# devkit.net
KiCad netlist of a schematic drawn in EAGLE
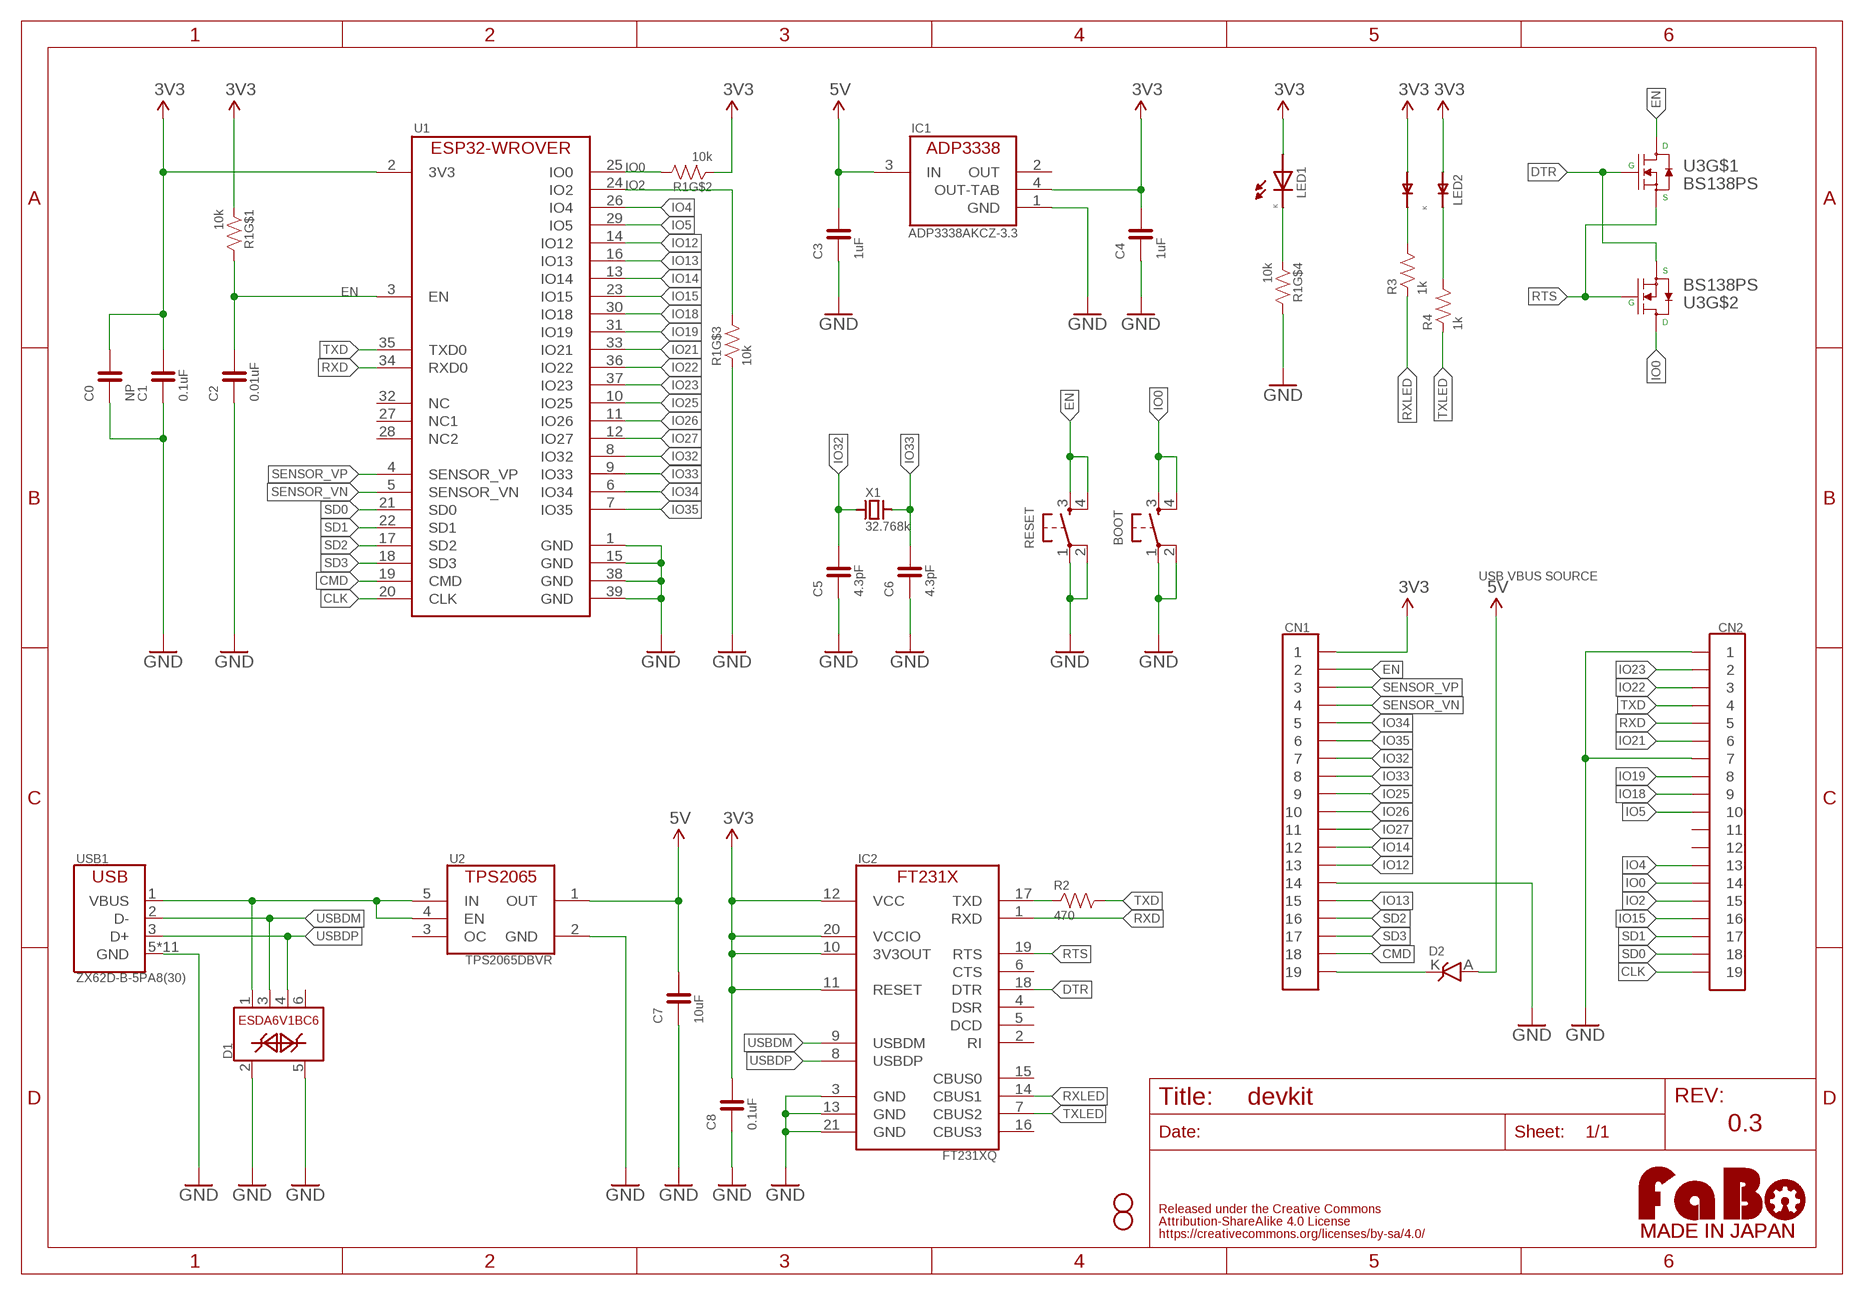
[diagram p0: schematic, sheet 1]

(export (version "E")
  (design (tool "Eeschema 10.0.6"))
  (components
    (comp (ref "BOOT")
      (value "TACTILE-KMR2")
      (footprint "eagle-import:KMR2-TACT")
      (libsource (lib "eagle-import") (part "TACTILE-KMR2"))
    )
    (comp (ref "C0")
      (value "NP")
      (footprint "eagle-import:MULTIPAD0603")
      (libsource (lib "eagle-import") (part "CAPACITOR-M"))
    )
    (comp (ref "C1")
      (value "0.1uF")
      (footprint "eagle-import:EIA0603")
      (libsource (lib "eagle-import") (part "CAPACITOR-0603"))
    )
    (comp (ref "C2")
      (value "0.01uF")
      (footprint "eagle-import:EIA0603")
      (libsource (lib "eagle-import") (part "CAPACITOR-0603"))
    )
    (comp (ref "C3")
      (value "1uF")
      (footprint "eagle-import:EIA0603")
      (libsource (lib "eagle-import") (part "CAPACITOR-0603"))
    )
    (comp (ref "C4")
      (value "1uF")
      (footprint "eagle-import:EIA0603")
      (libsource (lib "eagle-import") (part "CAPACITOR-0603"))
    )
    (comp (ref "C5")
      (value "4.3pF")
      (footprint "eagle-import:EIA0603")
      (libsource (lib "eagle-import") (part "CAPACITOR-0603"))
    )
    (comp (ref "C6")
      (value "4.3pF")
      (footprint "eagle-import:EIA0603")
      (libsource (lib "eagle-import") (part "CAPACITOR-0603"))
    )
    (comp (ref "C7")
      (value "10uF")
      (footprint "eagle-import:EIA0603")
      (libsource (lib "eagle-import") (part "CAPACITOR-0603"))
    )
    (comp (ref "C8")
      (value "0.1uF")
      (footprint "eagle-import:EIA0603")
      (libsource (lib "eagle-import") (part "CAPACITOR-0603"))
    )
    (comp (ref "CN1")
      (value "PIN_1X19")
      (footprint "eagle-import:PIN_1X19")
      (libsource (lib "eagle-import") (part "PIN_1X19"))
    )
    (comp (ref "CN2")
      (value "PIN_1X19")
      (footprint "eagle-import:PIN_1X19")
      (libsource (lib "eagle-import") (part "PIN_1X19"))
    )
    (comp (ref "D1")
      (value "ESDA6V1BC6")
      (footprint "eagle-import:SOT-23-6L")
      (libsource (lib "eagle-import") (part "ESDA6V1BC6"))
    )
    (comp (ref "D2")
      (value "DIODE_SCHOTTKY-RB161MM-20")
      (footprint "eagle-import:SOD-123FL_RB161MM-20")
      (libsource (lib "eagle-import") (part "DIODE_SCHOTTKY-RB161MM-20"))
    )
    (comp (ref "FID1")
      (value "FIDUCIAL-TOP")
      (footprint "eagle-import:FIDUCIAL_15_TOP")
      (libsource (lib "eagle-import") (part "FIDUCIAL-TOP"))
    )
    (comp (ref "FID2")
      (value "FIDUCIAL-TOP")
      (footprint "eagle-import:FIDUCIAL_15_TOP")
      (libsource (lib "eagle-import") (part "FIDUCIAL-TOP"))
    )
    (comp (ref "IC1")
      (value "ADP3338AKCZ-3.3")
      (footprint "eagle-import:SOT-223-KC3")
      (libsource (lib "eagle-import") (part "ADP3338AKCZ"))
    )
    (comp (ref "IC2")
      (value "FT231XQ")
      (footprint "eagle-import:QFN-20")
      (libsource (lib "eagle-import") (part "FT231XQ"))
    )
    (comp (ref "LED1")
      (value "LED-0603")
      (footprint "eagle-import:LED_0603")
      (libsource (lib "eagle-import") (part "LED-0603"))
    )
    (comp (ref "LED2")
      (value "HSMF-C16X")
      (footprint "eagle-import:HSMF-C16X")
      (libsource (lib "eagle-import") (part "HSMF-C16X"))
    )
    (comp (ref "LOGO1")
      (value "LOGO_FABO-M_BOTTOM")
      (footprint "eagle-import:LOGO_FABO_M_BOTTOM")
      (libsource (lib "eagle-import") (part "LOGO_FABO-M_BOTTOM"))
    )
    (comp (ref "R1")
      (value "10k")
      (footprint "eagle-import:EXBV8V")
      (libsource (lib "eagle-import") (part "RESISTOR_ARRAY"))
    )
    (comp (ref "R2")
      (value "470")
      (footprint "eagle-import:EIA0603")
      (libsource (lib "eagle-import") (part "RESISTOR-0603"))
    )
    (comp (ref "R3")
      (value "1k")
      (footprint "eagle-import:EIA0603")
      (libsource (lib "eagle-import") (part "RESISTOR-0603"))
    )
    (comp (ref "R4")
      (value "1k")
      (footprint "eagle-import:EIA0603")
      (libsource (lib "eagle-import") (part "RESISTOR-0603"))
    )
    (comp (ref "RESET")
      (value "TACTILE-KMR2")
      (footprint "eagle-import:KMR2-TACT")
      (libsource (lib "eagle-import") (part "TACTILE-KMR2"))
    )
    (comp (ref "U1")
      (value "ESP32-WROVER-B")
      (footprint "eagle-import:ESP32-WROVER-B")
      (libsource (lib "eagle-import") (part "ESP32-WROVER-B"))
    )
    (comp (ref "U2")
      (value "TPS2065DBVR")
      (footprint "eagle-import:SOT-23-5")
      (libsource (lib "eagle-import") (part "TPS2065DBV"))
    )
    (comp (ref "U3")
      (value "BS138PS")
      (footprint "eagle-import:SOT-363")
      (libsource (lib "eagle-import") (part "BS138PS"))
    )
    (comp (ref "USB1")
      (value "ZX62D-B-5PA8(30)")
      (footprint "eagle-import:ZX62D-B-5PA8")
      (libsource (lib "eagle-import") (part "USB-ZX62D"))
    )
    (comp (ref "X1")
      (value "32.768k")
      (footprint "eagle-import:ABS07")
      (libsource (lib "eagle-import") (part "CRYSTAL-ABS07"))
    )
  )
  (nets
    (net (code "1") (name "3V3") (class "Default")
      (node (ref "C0") (pin "2") (pinfunction "2_2") (pintype "passive"))
      (node (ref "C1") (pin "2") (pinfunction "2_2") (pintype "passive"))
      (node (ref "C4") (pin "2") (pinfunction "2_2") (pintype "passive"))
      (node (ref "C8") (pin "2") (pinfunction "2_2") (pintype "passive"))
      (node (ref "CN1") (pin "1") (pinfunction "1_1") (pintype "bidirectional"))
      (node (ref "IC1") (pin "4") (pinfunction "OUT-TAB_4") (pintype "bidirectional"))
      (node (ref "IC2") (pin "10") (pinfunction "3V3OUT_10") (pintype "bidirectional"))
      (node (ref "IC2") (pin "11") (pinfunction "RESET_11") (pintype "bidirectional"))
      (node (ref "IC2") (pin "12") (pinfunction "VCC_12") (pintype "bidirectional"))
      (node (ref "IC2") (pin "20") (pinfunction "VCCIO_20") (pintype "bidirectional"))
      (node (ref "LED1") (pin "A") (pinfunction "ANODE_A") (pintype "passive"))
      (node (ref "LED2") (pin "1") (pinfunction "A1_1") (pintype "passive"))
      (node (ref "LED2") (pin "2") (pinfunction "A2_2") (pintype "bidirectional"))
      (node (ref "R1") (pin "1") (pinfunction "1_1") (pintype "bidirectional"))
      (node (ref "R1") (pin "2") (pinfunction "1_2") (pintype "bidirectional"))
      (node (ref "U1") (pin "2") (pinfunction "3V3_2") (pintype "bidirectional"))
    )
    (net (code "2") (name "5V") (class "Default")
      (node (ref "C3") (pin "2") (pinfunction "2_2") (pintype "passive"))
      (node (ref "C7") (pin "2") (pinfunction "2_2") (pintype "passive"))
      (node (ref "D2") (pin "A") (pinfunction "A_A") (pintype "bidirectional"))
      (node (ref "IC1") (pin "3") (pinfunction "IN_3") (pintype "bidirectional"))
      (node (ref "U2") (pin "1") (pinfunction "OUT_1") (pintype "bidirectional"))
    )
    (net (code "3") (name "CLK") (class "Default")
      (node (ref "CN2") (pin "19") (pinfunction "19_19") (pintype "bidirectional"))
      (node (ref "U1") (pin "20") (pinfunction "CLK_20") (pintype "bidirectional"))
    )
    (net (code "4") (name "CMD") (class "Default")
      (node (ref "CN1") (pin "18") (pinfunction "18_18") (pintype "bidirectional"))
      (node (ref "U1") (pin "19") (pinfunction "CMD_19") (pintype "bidirectional"))
    )
    (net (code "5") (name "DTR") (class "Default")
      (node (ref "IC2") (pin "18") (pinfunction "DTR_18") (pintype "bidirectional"))
      (node (ref "U3") (pin "2") (pinfunction "G_2") (pintype "passive"))
      (node (ref "U3") (pin "4") (pinfunction "S_4") (pintype "passive"))
    )
    (net (code "6") (name "EN") (class "Default")
      (node (ref "C2") (pin "2") (pinfunction "2_2") (pintype "passive"))
      (node (ref "CN1") (pin "2") (pinfunction "2_2") (pintype "bidirectional"))
      (node (ref "R1") (pin "8") (pinfunction "2_8") (pintype "bidirectional"))
      (node (ref "RESET") (pin "3") (pinfunction "3_3") (pintype "passive"))
      (node (ref "RESET") (pin "4") (pinfunction "4_4") (pintype "passive"))
      (node (ref "U1") (pin "3") (pinfunction "EN_3") (pintype "bidirectional"))
      (node (ref "U3") (pin "6") (pinfunction "D_6") (pintype "passive"))
    )
    (net (code "7") (name "GND") (class "Default")
      (node (ref "BOOT") (pin "1") (pinfunction "1_1") (pintype "passive"))
      (node (ref "BOOT") (pin "2") (pinfunction "2_2") (pintype "passive"))
      (node (ref "C0") (pin "1") (pinfunction "1_1") (pintype "passive"))
      (node (ref "C1") (pin "1") (pinfunction "1_1") (pintype "passive"))
      (node (ref "C2") (pin "1") (pinfunction "1_1") (pintype "passive"))
      (node (ref "C3") (pin "1") (pinfunction "1_1") (pintype "passive"))
      (node (ref "C4") (pin "1") (pinfunction "1_1") (pintype "passive"))
      (node (ref "C5") (pin "1") (pinfunction "1_1") (pintype "passive"))
      (node (ref "C6") (pin "1") (pinfunction "1_1") (pintype "passive"))
      (node (ref "C7") (pin "1") (pinfunction "1_1") (pintype "passive"))
      (node (ref "C8") (pin "1") (pinfunction "1_1") (pintype "passive"))
      (node (ref "CN1") (pin "14") (pinfunction "14_14") (pintype "bidirectional"))
      (node (ref "CN2") (pin "1") (pinfunction "1_1") (pintype "bidirectional"))
      (node (ref "CN2") (pin "7") (pinfunction "7_7") (pintype "bidirectional"))
      (node (ref "D1") (pin "2") (pinfunction "2_2") (pintype "bidirectional"))
      (node (ref "D1") (pin "5") (pinfunction "5_5") (pintype "bidirectional"))
      (node (ref "IC1") (pin "1") (pinfunction "GND_1") (pintype "bidirectional"))
      (node (ref "IC2") (pin "13") (pinfunction "GND_13") (pintype "bidirectional"))
      (node (ref "IC2") (pin "21") (pinfunction "GND_21") (pintype "bidirectional"))
      (node (ref "IC2") (pin "3") (pinfunction "GND_3") (pintype "bidirectional"))
      (node (ref "R1") (pin "3") (pinfunction "1_3") (pintype "bidirectional"))
      (node (ref "R1") (pin "5") (pinfunction "2_5") (pintype "bidirectional"))
      (node (ref "RESET") (pin "1") (pinfunction "1_1") (pintype "passive"))
      (node (ref "RESET") (pin "2") (pinfunction "2_2") (pintype "passive"))
      (node (ref "U1") (pin "1") (pinfunction "GND_1") (pintype "bidirectional"))
      (node (ref "U1") (pin "15") (pinfunction "GND_15") (pintype "bidirectional"))
      (node (ref "U1") (pin "38") (pinfunction "GND_38") (pintype "bidirectional"))
      (node (ref "U1") (pin "39") (pinfunction "GND_39") (pintype "bidirectional"))
      (node (ref "U2") (pin "2") (pinfunction "GND_2") (pintype "bidirectional"))
      (node (ref "USB1") (pin "5") (pinfunction "GND_5") (pintype "bidirectional"))
      (node (ref "USB1") (pin "B1") (pinfunction "GND_B1") (pintype "bidirectional"))
      (node (ref "USB1") (pin "B2") (pinfunction "GND_B2") (pintype "bidirectional"))
      (node (ref "USB1") (pin "B3") (pinfunction "GND_B3") (pintype "bidirectional"))
      (node (ref "USB1") (pin "B4") (pinfunction "GND_B4") (pintype "bidirectional"))
      (node (ref "USB1") (pin "T1") (pinfunction "GND_T1") (pintype "bidirectional"))
      (node (ref "USB1") (pin "T2") (pinfunction "GND_T2") (pintype "bidirectional"))
      (node (ref "USB1") (pin "T3") (pinfunction "GND_T3") (pintype "bidirectional"))
      (node (ref "USB1") (pin "T4") (pinfunction "GND_T4") (pintype "bidirectional"))
      (node (ref "USB1") (pin "T5") (pinfunction "GND_T5") (pintype "bidirectional"))
      (node (ref "USB1") (pin "T6") (pinfunction "GND_T6") (pintype "bidirectional"))
    )
    (net (code "8") (name "IO0") (class "Default")
      (node (ref "BOOT") (pin "3") (pinfunction "3_3") (pintype "passive"))
      (node (ref "BOOT") (pin "4") (pinfunction "4_4") (pintype "passive"))
      (node (ref "CN2") (pin "14") (pinfunction "14_14") (pintype "bidirectional"))
      (node (ref "R1") (pin "7") (pinfunction "2_7") (pintype "bidirectional"))
      (node (ref "U1") (pin "25") (pinfunction "IO0_25") (pintype "bidirectional"))
      (node (ref "U3") (pin "3") (pinfunction "D_3") (pintype "passive"))
    )
    (net (code "9") (name "IO2") (class "Default")
      (node (ref "CN2") (pin "15") (pinfunction "15_15") (pintype "bidirectional"))
      (node (ref "R1") (pin "6") (pinfunction "2_6") (pintype "bidirectional"))
      (node (ref "U1") (pin "24") (pinfunction "IO2_24") (pintype "bidirectional"))
    )
    (net (code "10") (name "IO4") (class "Default")
      (node (ref "CN2") (pin "13") (pinfunction "13_13") (pintype "bidirectional"))
      (node (ref "U1") (pin "26") (pinfunction "IO4_26") (pintype "bidirectional"))
    )
    (net (code "11") (name "IO5") (class "Default")
      (node (ref "CN2") (pin "10") (pinfunction "10_10") (pintype "bidirectional"))
      (node (ref "U1") (pin "29") (pinfunction "IO5_29") (pintype "bidirectional"))
    )
    (net (code "12") (name "IO12") (class "Default")
      (node (ref "CN1") (pin "13") (pinfunction "13_13") (pintype "bidirectional"))
      (node (ref "U1") (pin "14") (pinfunction "IO12_14") (pintype "bidirectional"))
    )
    (net (code "13") (name "IO13") (class "Default")
      (node (ref "CN1") (pin "15") (pinfunction "15_15") (pintype "bidirectional"))
      (node (ref "U1") (pin "16") (pinfunction "IO13_16") (pintype "bidirectional"))
    )
    (net (code "14") (name "IO14") (class "Default")
      (node (ref "CN1") (pin "12") (pinfunction "12_12") (pintype "bidirectional"))
      (node (ref "U1") (pin "13") (pinfunction "IO14_13") (pintype "bidirectional"))
    )
    (net (code "15") (name "IO15") (class "Default")
      (node (ref "CN2") (pin "16") (pinfunction "16_16") (pintype "bidirectional"))
      (node (ref "U1") (pin "23") (pinfunction "IO15_23") (pintype "bidirectional"))
    )
    (net (code "16") (name "IO18") (class "Default")
      (node (ref "CN2") (pin "9") (pinfunction "9_9") (pintype "bidirectional"))
      (node (ref "U1") (pin "30") (pinfunction "IO18_30") (pintype "bidirectional"))
    )
    (net (code "17") (name "IO19") (class "Default")
      (node (ref "CN2") (pin "8") (pinfunction "8_8") (pintype "bidirectional"))
      (node (ref "U1") (pin "31") (pinfunction "IO19_31") (pintype "bidirectional"))
    )
    (net (code "18") (name "IO21") (class "Default")
      (node (ref "CN2") (pin "6") (pinfunction "6_6") (pintype "bidirectional"))
      (node (ref "U1") (pin "33") (pinfunction "IO21_33") (pintype "bidirectional"))
    )
    (net (code "19") (name "IO22") (class "Default")
      (node (ref "CN2") (pin "3") (pinfunction "3_3") (pintype "bidirectional"))
      (node (ref "U1") (pin "36") (pinfunction "IO22_36") (pintype "bidirectional"))
    )
    (net (code "20") (name "IO23") (class "Default")
      (node (ref "CN2") (pin "2") (pinfunction "2_2") (pintype "bidirectional"))
      (node (ref "U1") (pin "37") (pinfunction "IO23_37") (pintype "bidirectional"))
    )
    (net (code "21") (name "IO25") (class "Default")
      (node (ref "CN1") (pin "9") (pinfunction "9_9") (pintype "bidirectional"))
      (node (ref "U1") (pin "10") (pinfunction "IO25_10") (pintype "bidirectional"))
    )
    (net (code "22") (name "IO26") (class "Default")
      (node (ref "CN1") (pin "10") (pinfunction "10_10") (pintype "bidirectional"))
      (node (ref "U1") (pin "11") (pinfunction "IO26_11") (pintype "bidirectional"))
    )
    (net (code "23") (name "IO27") (class "Default")
      (node (ref "CN1") (pin "11") (pinfunction "11_11") (pintype "bidirectional"))
      (node (ref "U1") (pin "12") (pinfunction "IO27_12") (pintype "bidirectional"))
    )
    (net (code "24") (name "IO32") (class "Default")
      (node (ref "C5") (pin "2") (pinfunction "2_2") (pintype "passive"))
      (node (ref "CN1") (pin "7") (pinfunction "7_7") (pintype "bidirectional"))
      (node (ref "U1") (pin "8") (pinfunction "IO32_8") (pintype "bidirectional"))
      (node (ref "X1") (pin "1") (pinfunction "P$1_1") (pintype "bidirectional"))
    )
    (net (code "25") (name "IO33") (class "Default")
      (node (ref "C6") (pin "2") (pinfunction "2_2") (pintype "passive"))
      (node (ref "CN1") (pin "8") (pinfunction "8_8") (pintype "bidirectional"))
      (node (ref "U1") (pin "9") (pinfunction "IO33_9") (pintype "bidirectional"))
      (node (ref "X1") (pin "2") (pinfunction "P$2_2") (pintype "bidirectional"))
    )
    (net (code "26") (name "IO34") (class "Default")
      (node (ref "CN1") (pin "5") (pinfunction "5_5") (pintype "bidirectional"))
      (node (ref "U1") (pin "6") (pinfunction "IO34_6") (pintype "bidirectional"))
    )
    (net (code "27") (name "IO35") (class "Default")
      (node (ref "CN1") (pin "6") (pinfunction "6_6") (pintype "bidirectional"))
      (node (ref "U1") (pin "7") (pinfunction "IO35_7") (pintype "bidirectional"))
    )
    (net (code "28") (name "Net-(CN1-Pad19)") (class "Default")
      (node (ref "CN1") (pin "19") (pinfunction "19_19") (pintype "bidirectional"))
      (node (ref "D2") (pin "K") (pinfunction "K_K") (pintype "bidirectional"))
    )
    (net (code "29") (name "Net-(IC2-TXD)") (class "Default")
      (node (ref "IC2") (pin "17") (pinfunction "TXD_17") (pintype "bidirectional"))
      (node (ref "R2") (pin "1") (pinfunction "1_1") (pintype "bidirectional"))
    )
    (net (code "30") (name "Net-(LED1-CATHODE)") (class "Default")
      (node (ref "LED1") (pin "K") (pinfunction "CATHODE_K") (pintype "passive"))
      (node (ref "R1") (pin "4") (pinfunction "1_4") (pintype "bidirectional"))
    )
    (net (code "31") (name "Net-(LED2-K1)") (class "Default")
      (node (ref "LED2") (pin "3") (pinfunction "K1_3") (pintype "passive"))
      (node (ref "R4") (pin "2") (pinfunction "2_2") (pintype "bidirectional"))
    )
    (net (code "32") (name "Net-(LED2-K2)") (class "Default")
      (node (ref "LED2") (pin "4") (pinfunction "K2_4") (pintype "bidirectional"))
      (node (ref "R3") (pin "2") (pinfunction "2_2") (pintype "bidirectional"))
    )
    (net (code "33") (name "Net-(U2-EN)") (class "Default")
      (node (ref "D1") (pin "1") (pinfunction "1_1") (pintype "bidirectional"))
      (node (ref "U2") (pin "4") (pinfunction "EN_4") (pintype "bidirectional"))
      (node (ref "U2") (pin "5") (pinfunction "IN_5") (pintype "bidirectional"))
      (node (ref "USB1") (pin "1") (pinfunction "VBUS_1") (pintype "bidirectional"))
    )
    (net (code "34") (name "RTS") (class "Default")
      (node (ref "IC2") (pin "19") (pinfunction "RTS_19") (pintype "bidirectional"))
      (node (ref "U3") (pin "1") (pinfunction "S_1") (pintype "passive"))
      (node (ref "U3") (pin "5") (pinfunction "G_5") (pintype "passive"))
    )
    (net (code "35") (name "RXD") (class "Default")
      (node (ref "CN2") (pin "5") (pinfunction "5_5") (pintype "bidirectional"))
      (node (ref "IC2") (pin "1") (pinfunction "RXD_1") (pintype "bidirectional"))
      (node (ref "U1") (pin "34") (pinfunction "RXD0_34") (pintype "bidirectional"))
    )
    (net (code "36") (name "RXLED") (class "Default")
      (node (ref "IC2") (pin "14") (pinfunction "CBUS1_14") (pintype "bidirectional"))
      (node (ref "R3") (pin "1") (pinfunction "1_1") (pintype "bidirectional"))
    )
    (net (code "37") (name "SD0") (class "Default")
      (node (ref "CN2") (pin "18") (pinfunction "18_18") (pintype "bidirectional"))
      (node (ref "U1") (pin "21") (pinfunction "SD0_21") (pintype "bidirectional"))
    )
    (net (code "38") (name "SD1") (class "Default")
      (node (ref "CN2") (pin "17") (pinfunction "17_17") (pintype "bidirectional"))
      (node (ref "U1") (pin "22") (pinfunction "SD1_22") (pintype "bidirectional"))
    )
    (net (code "39") (name "SD2") (class "Default")
      (node (ref "CN1") (pin "16") (pinfunction "16_16") (pintype "bidirectional"))
      (node (ref "U1") (pin "17") (pinfunction "SD2_17") (pintype "bidirectional"))
    )
    (net (code "40") (name "SD3") (class "Default")
      (node (ref "CN1") (pin "17") (pinfunction "17_17") (pintype "bidirectional"))
      (node (ref "U1") (pin "18") (pinfunction "SD3_18") (pintype "bidirectional"))
    )
    (net (code "41") (name "SENSOR_VN") (class "Default")
      (node (ref "CN1") (pin "4") (pinfunction "4_4") (pintype "bidirectional"))
      (node (ref "U1") (pin "5") (pinfunction "SENSOR_VN_5") (pintype "bidirectional"))
    )
    (net (code "42") (name "SENSOR_VP") (class "Default")
      (node (ref "CN1") (pin "3") (pinfunction "3_3") (pintype "bidirectional"))
      (node (ref "U1") (pin "4") (pinfunction "SENSOR_VP_4") (pintype "bidirectional"))
    )
    (net (code "43") (name "TXD") (class "Default")
      (node (ref "CN2") (pin "4") (pinfunction "4_4") (pintype "bidirectional"))
      (node (ref "R2") (pin "2") (pinfunction "2_2") (pintype "bidirectional"))
      (node (ref "U1") (pin "35") (pinfunction "TXD0_35") (pintype "bidirectional"))
    )
    (net (code "44") (name "TXLED") (class "Default")
      (node (ref "IC2") (pin "7") (pinfunction "CBUS2_7") (pintype "bidirectional"))
      (node (ref "R4") (pin "1") (pinfunction "1_1") (pintype "bidirectional"))
    )
    (net (code "45") (name "USBDM") (class "Default")
      (node (ref "D1") (pin "3") (pinfunction "3_3") (pintype "bidirectional"))
      (node (ref "IC2") (pin "9") (pinfunction "USBDM_9") (pintype "bidirectional"))
      (node (ref "USB1") (pin "2") (pinfunction "D-_2") (pintype "bidirectional"))
    )
    (net (code "46") (name "USBDP") (class "Default")
      (node (ref "D1") (pin "4") (pinfunction "4_4") (pintype "bidirectional"))
      (node (ref "IC2") (pin "8") (pinfunction "USBDP_8") (pintype "bidirectional"))
      (node (ref "USB1") (pin "3") (pinfunction "D+_3") (pintype "bidirectional"))
    )
    (net (code "47") (name "unconnected-(CN2-Pad11)") (class "Default")
      (node (ref "CN2") (pin "11") (pinfunction "11_11") (pintype "bidirectional"))
    )
    (net (code "48") (name "unconnected-(CN2-Pad12)") (class "Default")
      (node (ref "CN2") (pin "12") (pinfunction "12_12") (pintype "bidirectional"))
    )
    (net (code "49") (name "unconnected-(D1-Pad6)") (class "Default")
      (node (ref "D1") (pin "6") (pinfunction "6_6") (pintype "bidirectional"))
    )
    (net (code "50") (name "unconnected-(IC1-OUT-Pad2)") (class "Default")
      (node (ref "IC1") (pin "2") (pinfunction "OUT_2") (pintype "bidirectional"))
    )
    (net (code "51") (name "unconnected-(IC2-CBUS0-Pad15)") (class "Default")
      (node (ref "IC2") (pin "15") (pinfunction "CBUS0_15") (pintype "bidirectional"))
    )
    (net (code "52") (name "unconnected-(IC2-CBUS3-Pad16)") (class "Default")
      (node (ref "IC2") (pin "16") (pinfunction "CBUS3_16") (pintype "bidirectional"))
    )
    (net (code "53") (name "unconnected-(IC2-CTS-Pad6)") (class "Default")
      (node (ref "IC2") (pin "6") (pinfunction "CTS_6") (pintype "bidirectional"))
    )
    (net (code "54") (name "unconnected-(IC2-DCD-Pad5)") (class "Default")
      (node (ref "IC2") (pin "5") (pinfunction "DCD_5") (pintype "bidirectional"))
    )
    (net (code "55") (name "unconnected-(IC2-DSR-Pad4)") (class "Default")
      (node (ref "IC2") (pin "4") (pinfunction "DSR_4") (pintype "bidirectional"))
    )
    (net (code "56") (name "unconnected-(IC2-RI-Pad2)") (class "Default")
      (node (ref "IC2") (pin "2") (pinfunction "RI_2") (pintype "bidirectional"))
    )
    (net (code "57") (name "unconnected-(U1-NC-Pad32)") (class "Default")
      (node (ref "U1") (pin "32") (pinfunction "NC_32") (pintype "bidirectional"))
    )
    (net (code "58") (name "unconnected-(U1-NC1-Pad27)") (class "Default")
      (node (ref "U1") (pin "27") (pinfunction "NC1_27") (pintype "bidirectional"))
    )
    (net (code "59") (name "unconnected-(U1-NC2-Pad28)") (class "Default")
      (node (ref "U1") (pin "28") (pinfunction "NC2_28") (pintype "bidirectional"))
    )
    (net (code "60") (name "unconnected-(U2-OC-Pad3)") (class "Default")
      (node (ref "U2") (pin "3") (pinfunction "OC_3") (pintype "bidirectional"))
    )
  )
)
